# Anemometor_ResDiv1.net
KiCad netlist of a schematic drawn in Altium Designer
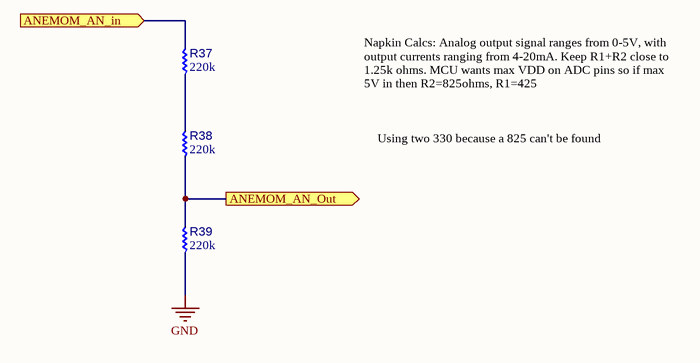
[diagram p0: Anemometor_ResDiv1.SchDoc]

(export (version "E")
  (design (tool "Eeschema 10.0.6"))
  (components
    (comp (ref "R37")
      (value "220k")
      (footprint "New footprint 1")
      (description "Res Thick Film 0603 220K Ohm 1% 0.1W(1/10W) ±100ppm/C Pad SMD Automotive T/R")
      (fields (field (name "TOLERANCE") "1%") (field (name "Comment") "RMCF0603FT220K"))
      (libsource (lib "University of Calgary - SOAR") (part "RES-2"))
    )
    (comp (ref "R38")
      (value "220k")
      (footprint "New footprint 1")
      (description "Res Thick Film 0603 220K Ohm 1% 0.1W(1/10W) ±100ppm/C Pad SMD Automotive T/R")
      (fields (field (name "TOLERANCE") "1%") (field (name "Comment") "RMCF0603FT220K"))
      (libsource (lib "University of Calgary - SOAR") (part "RES-2"))
    )
    (comp (ref "R39")
      (value "220k")
      (footprint "New footprint 1")
      (description "Res Thick Film 0603 220K Ohm 1% 0.1W(1/10W) ±100ppm/C Pad SMD Automotive T/R")
      (fields (field (name "TOLERANCE") "1%") (field (name "Comment") "RMCF0603FT220K"))
      (libsource (lib "University of Calgary - SOAR") (part "RES-2"))
    )
  )
  (nets
    (net (code "1") (name "/ANEMOM_AN_Out") (class "Default")
      (node (ref "R38") (pin "1") (pinfunction "1_1") (pintype "passive"))
      (node (ref "R39") (pin "2") (pinfunction "2_2") (pintype "passive"))
    )
    (net (code "2") (name "/ANEMOM_AN_in") (class "Default")
      (node (ref "R37") (pin "2") (pinfunction "2_2") (pintype "passive"))
    )
    (net (code "3") (name "GND") (class "Default")
      (node (ref "R39") (pin "1") (pinfunction "1_1") (pintype "passive"))
    )
    (net (code "4") (name "Net-(R37-Pad1)") (class "Default")
      (node (ref "R37") (pin "1") (pinfunction "1_1") (pintype "passive"))
      (node (ref "R38") (pin "2") (pinfunction "2_2") (pintype "passive"))
    )
  )
)
